# SDRAM.net
KiCad netlist of a schematic drawn in Altium Designer
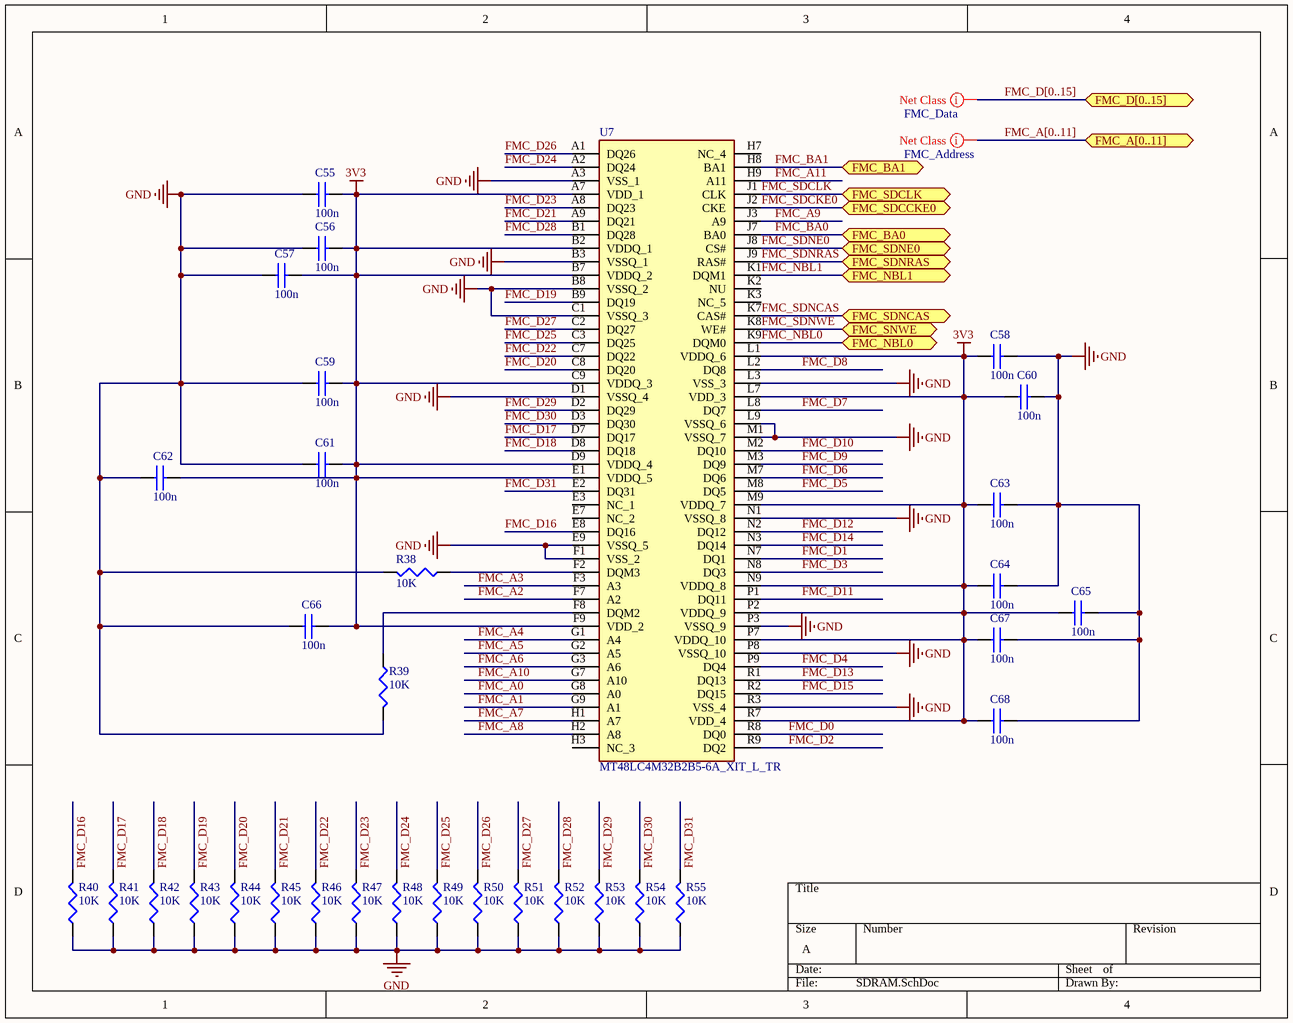
[diagram p0: SDRAM.SchDoc]

(export (version "E")
  (design (tool "Eeschema 10.0.6"))
  (components
    (comp (ref "C55")
      (value "100n")
      (footprint "C0402")
      (description "CAP CER .10UF 50V X5R 10% 0402")
      (fields
        (field (name "MANUFACTURER") "TDK Corporation")
        (field (name "MANUFACTURER PART NUMBER") "C1005X5R1H104K")
      )
      (libsource (lib "iMX6_Rex_Development_Baseboard_V1I1") (part "C1005X5R1H104K"))
    )
    (comp (ref "C56")
      (value "100n")
      (footprint "C0402")
      (description "CAP CER .10UF 50V X5R 10% 0402")
      (fields
        (field (name "MANUFACTURER") "TDK Corporation")
        (field (name "MANUFACTURER PART NUMBER") "C1005X5R1H104K")
      )
      (libsource (lib "iMX6_Rex_Development_Baseboard_V1I1") (part "C1005X5R1H104K"))
    )
    (comp (ref "C57")
      (value "100n")
      (footprint "C0402")
      (description "CAP CER .10UF 50V X5R 10% 0402")
      (fields
        (field (name "MANUFACTURER") "TDK Corporation")
        (field (name "MANUFACTURER PART NUMBER") "C1005X5R1H104K")
      )
      (libsource (lib "iMX6_Rex_Development_Baseboard_V1I1") (part "C1005X5R1H104K"))
    )
    (comp (ref "C58")
      (value "100n")
      (footprint "C0402")
      (description "CAP CER .10UF 50V X5R 10% 0402")
      (fields
        (field (name "MANUFACTURER") "TDK Corporation")
        (field (name "MANUFACTURER PART NUMBER") "C1005X5R1H104K")
      )
      (libsource (lib "iMX6_Rex_Development_Baseboard_V1I1") (part "C1005X5R1H104K"))
    )
    (comp (ref "C59")
      (value "100n")
      (footprint "C0402")
      (description "CAP CER .10UF 50V X5R 10% 0402")
      (fields
        (field (name "MANUFACTURER") "TDK Corporation")
        (field (name "MANUFACTURER PART NUMBER") "C1005X5R1H104K")
      )
      (libsource (lib "iMX6_Rex_Development_Baseboard_V1I1") (part "C1005X5R1H104K"))
    )
    (comp (ref "C60")
      (value "100n")
      (footprint "C0402")
      (description "CAP CER .10UF 50V X5R 10% 0402")
      (fields
        (field (name "MANUFACTURER") "TDK Corporation")
        (field (name "MANUFACTURER PART NUMBER") "C1005X5R1H104K")
      )
      (libsource (lib "iMX6_Rex_Development_Baseboard_V1I1") (part "C1005X5R1H104K"))
    )
    (comp (ref "C61")
      (value "100n")
      (footprint "C0402")
      (description "CAP CER .10UF 50V X5R 10% 0402")
      (fields
        (field (name "MANUFACTURER") "TDK Corporation")
        (field (name "MANUFACTURER PART NUMBER") "C1005X5R1H104K")
      )
      (libsource (lib "iMX6_Rex_Development_Baseboard_V1I1") (part "C1005X5R1H104K"))
    )
    (comp (ref "C62")
      (value "100n")
      (footprint "C0402")
      (description "CAP CER .10UF 50V X5R 10% 0402")
      (fields
        (field (name "MANUFACTURER") "TDK Corporation")
        (field (name "MANUFACTURER PART NUMBER") "C1005X5R1H104K")
      )
      (libsource (lib "iMX6_Rex_Development_Baseboard_V1I1") (part "C1005X5R1H104K"))
    )
    (comp (ref "C63")
      (value "100n")
      (footprint "C0402")
      (description "CAP CER .10UF 50V X5R 10% 0402")
      (fields
        (field (name "MANUFACTURER") "TDK Corporation")
        (field (name "MANUFACTURER PART NUMBER") "C1005X5R1H104K")
      )
      (libsource (lib "iMX6_Rex_Development_Baseboard_V1I1") (part "C1005X5R1H104K"))
    )
    (comp (ref "C64")
      (value "100n")
      (footprint "C0402")
      (description "CAP CER .10UF 50V X5R 10% 0402")
      (fields
        (field (name "MANUFACTURER") "TDK Corporation")
        (field (name "MANUFACTURER PART NUMBER") "C1005X5R1H104K")
      )
      (libsource (lib "iMX6_Rex_Development_Baseboard_V1I1") (part "C1005X5R1H104K"))
    )
    (comp (ref "C65")
      (value "100n")
      (footprint "C0402")
      (description "CAP CER .10UF 50V X5R 10% 0402")
      (fields
        (field (name "MANUFACTURER") "TDK Corporation")
        (field (name "MANUFACTURER PART NUMBER") "C1005X5R1H104K")
      )
      (libsource (lib "iMX6_Rex_Development_Baseboard_V1I1") (part "C1005X5R1H104K"))
    )
    (comp (ref "C66")
      (value "100n")
      (footprint "C0402")
      (description "CAP CER .10UF 50V X5R 10% 0402")
      (fields
        (field (name "MANUFACTURER") "TDK Corporation")
        (field (name "MANUFACTURER PART NUMBER") "C1005X5R1H104K")
      )
      (libsource (lib "iMX6_Rex_Development_Baseboard_V1I1") (part "C1005X5R1H104K"))
    )
    (comp (ref "C67")
      (value "100n")
      (footprint "C0402")
      (description "CAP CER .10UF 50V X5R 10% 0402")
      (fields
        (field (name "MANUFACTURER") "TDK Corporation")
        (field (name "MANUFACTURER PART NUMBER") "C1005X5R1H104K")
      )
      (libsource (lib "iMX6_Rex_Development_Baseboard_V1I1") (part "C1005X5R1H104K"))
    )
    (comp (ref "C68")
      (value "100n")
      (footprint "C0402")
      (description "CAP CER .10UF 50V X5R 10% 0402")
      (fields
        (field (name "MANUFACTURER") "TDK Corporation")
        (field (name "MANUFACTURER PART NUMBER") "C1005X5R1H104K")
      )
      (libsource (lib "iMX6_Rex_Development_Baseboard_V1I1") (part "C1005X5R1H104K"))
    )
    (comp (ref "R38")
      (value "10K")
      (footprint "R0402")
      (description "RES 10.0K OHM 1/16W 1% 0402 SMD")
      (fields
        (field (name "MANUFACTURER") "Yageo")
        (field (name "MANUFACTURER PART NUMBER") "RC0402FR-0710KL")
      )
      (libsource (lib "iMX6_Rex_Development_Baseboard_V1I1") (part "RC0402FR-0710KL"))
    )
    (comp (ref "R39")
      (value "10K")
      (footprint "R0402")
      (description "RES 10.0K OHM 1/16W 1% 0402 SMD")
      (fields
        (field (name "MANUFACTURER") "Yageo")
        (field (name "MANUFACTURER PART NUMBER") "RC0402FR-0710KL")
      )
      (libsource (lib "iMX6_Rex_Development_Baseboard_V1I1") (part "RC0402FR-0710KL"))
    )
    (comp (ref "R40")
      (value "10K")
      (footprint "R0402")
      (description "RES 10.0K OHM 1/16W 1% 0402 SMD")
      (fields
        (field (name "MANUFACTURER") "Yageo")
        (field (name "MANUFACTURER PART NUMBER") "RC0402FR-0710KL")
      )
      (libsource (lib "iMX6_Rex_Development_Baseboard_V1I1") (part "RC0402FR-0710KL"))
    )
    (comp (ref "R41")
      (value "10K")
      (footprint "R0402")
      (description "RES 10.0K OHM 1/16W 1% 0402 SMD")
      (fields
        (field (name "MANUFACTURER") "Yageo")
        (field (name "MANUFACTURER PART NUMBER") "RC0402FR-0710KL")
      )
      (libsource (lib "iMX6_Rex_Development_Baseboard_V1I1") (part "RC0402FR-0710KL"))
    )
    (comp (ref "R42")
      (value "10K")
      (footprint "R0402")
      (description "RES 10.0K OHM 1/16W 1% 0402 SMD")
      (fields
        (field (name "MANUFACTURER") "Yageo")
        (field (name "MANUFACTURER PART NUMBER") "RC0402FR-0710KL")
      )
      (libsource (lib "iMX6_Rex_Development_Baseboard_V1I1") (part "RC0402FR-0710KL"))
    )
    (comp (ref "R43")
      (value "10K")
      (footprint "R0402")
      (description "RES 10.0K OHM 1/16W 1% 0402 SMD")
      (fields
        (field (name "MANUFACTURER") "Yageo")
        (field (name "MANUFACTURER PART NUMBER") "RC0402FR-0710KL")
      )
      (libsource (lib "iMX6_Rex_Development_Baseboard_V1I1") (part "RC0402FR-0710KL"))
    )
    (comp (ref "R44")
      (value "10K")
      (footprint "R0402")
      (description "RES 10.0K OHM 1/16W 1% 0402 SMD")
      (fields
        (field (name "MANUFACTURER") "Yageo")
        (field (name "MANUFACTURER PART NUMBER") "RC0402FR-0710KL")
      )
      (libsource (lib "iMX6_Rex_Development_Baseboard_V1I1") (part "RC0402FR-0710KL"))
    )
    (comp (ref "R45")
      (value "10K")
      (footprint "R0402")
      (description "RES 10.0K OHM 1/16W 1% 0402 SMD")
      (fields
        (field (name "MANUFACTURER") "Yageo")
        (field (name "MANUFACTURER PART NUMBER") "RC0402FR-0710KL")
      )
      (libsource (lib "iMX6_Rex_Development_Baseboard_V1I1") (part "RC0402FR-0710KL"))
    )
    (comp (ref "R46")
      (value "10K")
      (footprint "R0402")
      (description "RES 10.0K OHM 1/16W 1% 0402 SMD")
      (fields
        (field (name "MANUFACTURER") "Yageo")
        (field (name "MANUFACTURER PART NUMBER") "RC0402FR-0710KL")
      )
      (libsource (lib "iMX6_Rex_Development_Baseboard_V1I1") (part "RC0402FR-0710KL"))
    )
    (comp (ref "R47")
      (value "10K")
      (footprint "R0402")
      (description "RES 10.0K OHM 1/16W 1% 0402 SMD")
      (fields
        (field (name "MANUFACTURER") "Yageo")
        (field (name "MANUFACTURER PART NUMBER") "RC0402FR-0710KL")
      )
      (libsource (lib "iMX6_Rex_Development_Baseboard_V1I1") (part "RC0402FR-0710KL"))
    )
    (comp (ref "R48")
      (value "10K")
      (footprint "R0402")
      (description "RES 10.0K OHM 1/16W 1% 0402 SMD")
      (fields
        (field (name "MANUFACTURER") "Yageo")
        (field (name "MANUFACTURER PART NUMBER") "RC0402FR-0710KL")
      )
      (libsource (lib "iMX6_Rex_Development_Baseboard_V1I1") (part "RC0402FR-0710KL"))
    )
    (comp (ref "R49")
      (value "10K")
      (footprint "R0402")
      (description "RES 10.0K OHM 1/16W 1% 0402 SMD")
      (fields
        (field (name "MANUFACTURER") "Yageo")
        (field (name "MANUFACTURER PART NUMBER") "RC0402FR-0710KL")
      )
      (libsource (lib "iMX6_Rex_Development_Baseboard_V1I1") (part "RC0402FR-0710KL"))
    )
    (comp (ref "R50")
      (value "10K")
      (footprint "R0402")
      (description "RES 10.0K OHM 1/16W 1% 0402 SMD")
      (fields
        (field (name "MANUFACTURER") "Yageo")
        (field (name "MANUFACTURER PART NUMBER") "RC0402FR-0710KL")
      )
      (libsource (lib "iMX6_Rex_Development_Baseboard_V1I1") (part "RC0402FR-0710KL"))
    )
    (comp (ref "R51")
      (value "10K")
      (footprint "R0402")
      (description "RES 10.0K OHM 1/16W 1% 0402 SMD")
      (fields
        (field (name "MANUFACTURER") "Yageo")
        (field (name "MANUFACTURER PART NUMBER") "RC0402FR-0710KL")
      )
      (libsource (lib "iMX6_Rex_Development_Baseboard_V1I1") (part "RC0402FR-0710KL"))
    )
    (comp (ref "R52")
      (value "10K")
      (footprint "R0402")
      (description "RES 10.0K OHM 1/16W 1% 0402 SMD")
      (fields
        (field (name "MANUFACTURER") "Yageo")
        (field (name "MANUFACTURER PART NUMBER") "RC0402FR-0710KL")
      )
      (libsource (lib "iMX6_Rex_Development_Baseboard_V1I1") (part "RC0402FR-0710KL"))
    )
    (comp (ref "R53")
      (value "10K")
      (footprint "R0402")
      (description "RES 10.0K OHM 1/16W 1% 0402 SMD")
      (fields
        (field (name "MANUFACTURER") "Yageo")
        (field (name "MANUFACTURER PART NUMBER") "RC0402FR-0710KL")
      )
      (libsource (lib "iMX6_Rex_Development_Baseboard_V1I1") (part "RC0402FR-0710KL"))
    )
    (comp (ref "R54")
      (value "10K")
      (footprint "R0402")
      (description "RES 10.0K OHM 1/16W 1% 0402 SMD")
      (fields
        (field (name "MANUFACTURER") "Yageo")
        (field (name "MANUFACTURER PART NUMBER") "RC0402FR-0710KL")
      )
      (libsource (lib "iMX6_Rex_Development_Baseboard_V1I1") (part "RC0402FR-0710KL"))
    )
    (comp (ref "R55")
      (value "10K")
      (footprint "R0402")
      (description "RES 10.0K OHM 1/16W 1% 0402 SMD")
      (fields
        (field (name "MANUFACTURER") "Yageo")
        (field (name "MANUFACTURER PART NUMBER") "RC0402FR-0710KL")
      )
      (libsource (lib "iMX6_Rex_Development_Baseboard_V1I1") (part "RC0402FR-0710KL"))
    )
    (comp (ref "U7")
      (value "MT48LC4M32B2B5-6A_XIT_L_TR")
      (footprint "SamacSys:BGA90C80P9X15_800X1300X70")
      (description "Integrated Circuit")
      (fields
        (field (name "MANUFACTURER_PART_NUMBER") "MT48LC4M32B2B5-6A XIT:L TR")
        (field (name "MOUSER PART NUMBER") "340-140098-REEL")
      )
      (libsource (lib "*") (part "MT48LC4M32B2B5-6A_XIT_L_TR"))
    )
  )
  (nets
    (net (code "1") (name "/FMC_A0") (class "Default")
      (node (ref "U7") (pin "G8") (pinfunction "A0_G8") (pintype "passive"))
    )
    (net (code "2") (name "/FMC_A1") (class "Default")
      (node (ref "U7") (pin "G9") (pinfunction "A1_G9") (pintype "passive"))
    )
    (net (code "3") (name "/FMC_A2") (class "Default")
      (node (ref "U7") (pin "F7") (pinfunction "A2_F7") (pintype "passive"))
    )
    (net (code "4") (name "/FMC_A3") (class "Default")
      (node (ref "U7") (pin "F3") (pinfunction "A3_F3") (pintype "passive"))
    )
    (net (code "5") (name "/FMC_A4") (class "Default")
      (node (ref "U7") (pin "G1") (pinfunction "A4_G1") (pintype "passive"))
    )
    (net (code "6") (name "/FMC_A5") (class "Default")
      (node (ref "U7") (pin "G2") (pinfunction "A5_G2") (pintype "passive"))
    )
    (net (code "7") (name "/FMC_A6") (class "Default")
      (node (ref "U7") (pin "G3") (pinfunction "A6_G3") (pintype "passive"))
    )
    (net (code "8") (name "/FMC_A7") (class "Default")
      (node (ref "U7") (pin "H1") (pinfunction "A7_H1") (pintype "passive"))
    )
    (net (code "9") (name "/FMC_A8") (class "Default")
      (node (ref "U7") (pin "H2") (pinfunction "A8_H2") (pintype "passive"))
    )
    (net (code "10") (name "/FMC_A9") (class "Default")
      (node (ref "U7") (pin "J3") (pinfunction "A9_J3") (pintype "passive"))
    )
    (net (code "11") (name "/FMC_A10") (class "Default")
      (node (ref "U7") (pin "G7") (pinfunction "A10_G7") (pintype "passive"))
    )
    (net (code "12") (name "/FMC_A11") (class "Default")
      (node (ref "U7") (pin "H9") (pinfunction "A11_H9") (pintype "passive"))
    )
    (net (code "14") (name "/FMC_BA0") (class "Default")
      (node (ref "U7") (pin "J7") (pinfunction "BA0_J7") (pintype "passive"))
    )
    (net (code "15") (name "/FMC_BA1") (class "Default")
      (node (ref "U7") (pin "H8") (pinfunction "BA1_H8") (pintype "passive"))
    )
    (net (code "16") (name "/FMC_D0") (class "Default")
      (node (ref "U7") (pin "R8") (pinfunction "DQ0_R8") (pintype "passive"))
    )
    (net (code "17") (name "/FMC_D1") (class "Default")
      (node (ref "U7") (pin "N7") (pinfunction "DQ1_N7") (pintype "passive"))
    )
    (net (code "18") (name "/FMC_D2") (class "Default")
      (node (ref "U7") (pin "R9") (pinfunction "DQ2_R9") (pintype "passive"))
    )
    (net (code "19") (name "/FMC_D3") (class "Default")
      (node (ref "U7") (pin "N8") (pinfunction "DQ3_N8") (pintype "passive"))
    )
    (net (code "20") (name "/FMC_D4") (class "Default")
      (node (ref "U7") (pin "P9") (pinfunction "DQ4_P9") (pintype "passive"))
    )
    (net (code "21") (name "/FMC_D5") (class "Default")
      (node (ref "U7") (pin "M8") (pinfunction "DQ5_M8") (pintype "passive"))
    )
    (net (code "22") (name "/FMC_D6") (class "Default")
      (node (ref "U7") (pin "M7") (pinfunction "DQ6_M7") (pintype "passive"))
    )
    (net (code "23") (name "/FMC_D7") (class "Default")
      (node (ref "U7") (pin "L8") (pinfunction "DQ7_L8") (pintype "passive"))
    )
    (net (code "24") (name "/FMC_D8") (class "Default")
      (node (ref "U7") (pin "L2") (pinfunction "DQ8_L2") (pintype "passive"))
    )
    (net (code "25") (name "/FMC_D9") (class "Default")
      (node (ref "U7") (pin "M3") (pinfunction "DQ9_M3") (pintype "passive"))
    )
    (net (code "26") (name "/FMC_D10") (class "Default")
      (node (ref "U7") (pin "M2") (pinfunction "DQ10_M2") (pintype "passive"))
    )
    (net (code "27") (name "/FMC_D11") (class "Default")
      (node (ref "U7") (pin "P1") (pinfunction "DQ11_P1") (pintype "passive"))
    )
    (net (code "28") (name "/FMC_D12") (class "Default")
      (node (ref "U7") (pin "N2") (pinfunction "DQ12_N2") (pintype "passive"))
    )
    (net (code "29") (name "/FMC_D13") (class "Default")
      (node (ref "U7") (pin "R1") (pinfunction "DQ13_R1") (pintype "passive"))
    )
    (net (code "30") (name "/FMC_D14") (class "Default")
      (node (ref "U7") (pin "N3") (pinfunction "DQ14_N3") (pintype "passive"))
    )
    (net (code "31") (name "/FMC_D15") (class "Default")
      (node (ref "U7") (pin "R2") (pinfunction "DQ15_R2") (pintype "passive"))
    )
    (net (code "32") (name "/FMC_D16") (class "Default")
      (node (ref "R40") (pin "2") (pinfunction "2_2") (pintype "passive"))
      (node (ref "U7") (pin "E8") (pinfunction "DQ16_E8") (pintype "passive"))
    )
    (net (code "33") (name "/FMC_D17") (class "Default")
      (node (ref "R41") (pin "2") (pinfunction "2_2") (pintype "passive"))
      (node (ref "U7") (pin "D7") (pinfunction "DQ17_D7") (pintype "passive"))
    )
    (net (code "34") (name "/FMC_D18") (class "Default")
      (node (ref "R42") (pin "2") (pinfunction "2_2") (pintype "passive"))
      (node (ref "U7") (pin "D8") (pinfunction "DQ18_D8") (pintype "passive"))
    )
    (net (code "35") (name "/FMC_D19") (class "Default")
      (node (ref "R43") (pin "2") (pinfunction "2_2") (pintype "passive"))
      (node (ref "U7") (pin "B9") (pinfunction "DQ19_B9") (pintype "passive"))
    )
    (net (code "36") (name "/FMC_D20") (class "Default")
      (node (ref "R44") (pin "2") (pinfunction "2_2") (pintype "passive"))
      (node (ref "U7") (pin "C8") (pinfunction "DQ20_C8") (pintype "passive"))
    )
    (net (code "37") (name "/FMC_D21") (class "Default")
      (node (ref "R45") (pin "2") (pinfunction "2_2") (pintype "passive"))
      (node (ref "U7") (pin "A9") (pinfunction "DQ21_A9") (pintype "passive"))
    )
    (net (code "38") (name "/FMC_D22") (class "Default")
      (node (ref "R46") (pin "2") (pinfunction "2_2") (pintype "passive"))
      (node (ref "U7") (pin "C7") (pinfunction "DQ22_C7") (pintype "passive"))
    )
    (net (code "39") (name "/FMC_D23") (class "Default")
      (node (ref "R47") (pin "2") (pinfunction "2_2") (pintype "passive"))
      (node (ref "U7") (pin "A8") (pinfunction "DQ23_A8") (pintype "passive"))
    )
    (net (code "40") (name "/FMC_D24") (class "Default")
      (node (ref "R48") (pin "2") (pinfunction "2_2") (pintype "passive"))
      (node (ref "U7") (pin "A2") (pinfunction "DQ24_A2") (pintype "passive"))
    )
    (net (code "41") (name "/FMC_D25") (class "Default")
      (node (ref "R49") (pin "2") (pinfunction "2_2") (pintype "passive"))
      (node (ref "U7") (pin "C3") (pinfunction "DQ25_C3") (pintype "passive"))
    )
    (net (code "42") (name "/FMC_D26") (class "Default")
      (node (ref "R50") (pin "2") (pinfunction "2_2") (pintype "passive"))
      (node (ref "U7") (pin "A1") (pinfunction "DQ26_A1") (pintype "passive"))
    )
    (net (code "43") (name "/FMC_D27") (class "Default")
      (node (ref "R51") (pin "2") (pinfunction "2_2") (pintype "passive"))
      (node (ref "U7") (pin "C2") (pinfunction "DQ27_C2") (pintype "passive"))
    )
    (net (code "44") (name "/FMC_D28") (class "Default")
      (node (ref "R52") (pin "2") (pinfunction "2_2") (pintype "passive"))
      (node (ref "U7") (pin "B1") (pinfunction "DQ28_B1") (pintype "passive"))
    )
    (net (code "45") (name "/FMC_D29") (class "Default")
      (node (ref "R53") (pin "2") (pinfunction "2_2") (pintype "passive"))
      (node (ref "U7") (pin "D2") (pinfunction "DQ29_D2") (pintype "passive"))
    )
    (net (code "46") (name "/FMC_D30") (class "Default")
      (node (ref "R54") (pin "2") (pinfunction "2_2") (pintype "passive"))
      (node (ref "U7") (pin "D3") (pinfunction "DQ30_D3") (pintype "passive"))
    )
    (net (code "47") (name "/FMC_D31") (class "Default")
      (node (ref "R55") (pin "2") (pinfunction "2_2") (pintype "passive"))
      (node (ref "U7") (pin "E2") (pinfunction "DQ31_E2") (pintype "passive"))
    )
    (net (code "49") (name "/FMC_NBL0") (class "Default")
      (node (ref "U7") (pin "K9") (pinfunction "DQM0_K9") (pintype "passive"))
    )
    (net (code "50") (name "/FMC_NBL1") (class "Default")
      (node (ref "U7") (pin "K1") (pinfunction "DQM1_K1") (pintype "passive"))
    )
    (net (code "51") (name "/FMC_SDCKE0") (class "Default")
      (node (ref "U7") (pin "J2") (pinfunction "CKE_J2") (pintype "passive"))
    )
    (net (code "52") (name "/FMC_SDCLK") (class "Default")
      (node (ref "U7") (pin "J1") (pinfunction "CLK_J1") (pintype "passive"))
    )
    (net (code "53") (name "/FMC_SDNCAS") (class "Default")
      (node (ref "U7") (pin "K7") (pinfunction "CAS#_K7") (pintype "passive"))
    )
    (net (code "54") (name "/FMC_SDNE0") (class "Default")
      (node (ref "U7") (pin "J8") (pinfunction "CS#_J8") (pintype "passive"))
    )
    (net (code "55") (name "/FMC_SDNRAS") (class "Default")
      (node (ref "U7") (pin "J9") (pinfunction "RAS#_J9") (pintype "passive"))
    )
    (net (code "56") (name "/FMC_SDNWE") (class "Default")
      (node (ref "U7") (pin "K8") (pinfunction "WE#_K8") (pintype "passive"))
    )
    (net (code "57") (name "3V3") (class "Default")
      (node (ref "C55") (pin "2") (pinfunction "2_2") (pintype "passive"))
      (node (ref "C56") (pin "2") (pinfunction "2_2") (pintype "passive"))
      (node (ref "C57") (pin "2") (pinfunction "2_2") (pintype "passive"))
      (node (ref "C58") (pin "1") (pinfunction "1_1") (pintype "passive"))
      (node (ref "C59") (pin "2") (pinfunction "2_2") (pintype "passive"))
      (node (ref "C60") (pin "1") (pinfunction "1_1") (pintype "passive"))
      (node (ref "C61") (pin "2") (pinfunction "2_2") (pintype "passive"))
      (node (ref "C62") (pin "2") (pinfunction "2_2") (pintype "passive"))
      (node (ref "C63") (pin "1") (pinfunction "1_1") (pintype "passive"))
      (node (ref "C64") (pin "1") (pinfunction "1_1") (pintype "passive"))
      (node (ref "C65") (pin "1") (pinfunction "1_1") (pintype "passive"))
      (node (ref "C66") (pin "2") (pinfunction "2_2") (pintype "passive"))
      (node (ref "C67") (pin "1") (pinfunction "1_1") (pintype "passive"))
      (node (ref "C68") (pin "1") (pinfunction "1_1") (pintype "passive"))
      (node (ref "U7") (pin "A7") (pinfunction "VDD_1_A7") (pintype "passive"))
      (node (ref "U7") (pin "B2") (pinfunction "VDDQ_1_B2") (pintype "passive"))
      (node (ref "U7") (pin "B7") (pinfunction "VDDQ_2_B7") (pintype "passive"))
      (node (ref "U7") (pin "C9") (pinfunction "VDDQ_3_C9") (pintype "passive"))
      (node (ref "U7") (pin "D9") (pinfunction "VDDQ_4_D9") (pintype "passive"))
      (node (ref "U7") (pin "E1") (pinfunction "VDDQ_5_E1") (pintype "passive"))
      (node (ref "U7") (pin "F9") (pinfunction "VDD_2_F9") (pintype "passive"))
      (node (ref "U7") (pin "L1") (pinfunction "VDDQ_6_L1") (pintype "passive"))
      (node (ref "U7") (pin "L7") (pinfunction "VDD_3_L7") (pintype "passive"))
      (node (ref "U7") (pin "M9") (pinfunction "VDDQ_7_M9") (pintype "passive"))
      (node (ref "U7") (pin "N9") (pinfunction "VDDQ_8_N9") (pintype "passive"))
      (node (ref "U7") (pin "P2") (pinfunction "VDDQ_9_P2") (pintype "passive"))
      (node (ref "U7") (pin "P7") (pinfunction "VDDQ_10_P7") (pintype "passive"))
      (node (ref "U7") (pin "R7") (pinfunction "VDD_4_R7") (pintype "passive"))
    )
    (net (code "58") (name "GND") (class "Default")
      (node (ref "C55") (pin "1") (pinfunction "1_1") (pintype "passive"))
      (node (ref "C56") (pin "1") (pinfunction "1_1") (pintype "passive"))
      (node (ref "C57") (pin "1") (pinfunction "1_1") (pintype "passive"))
      (node (ref "C58") (pin "2") (pinfunction "2_2") (pintype "passive"))
      (node (ref "C59") (pin "1") (pinfunction "1_1") (pintype "passive"))
      (node (ref "C60") (pin "2") (pinfunction "2_2") (pintype "passive"))
      (node (ref "C61") (pin "1") (pinfunction "1_1") (pintype "passive"))
      (node (ref "C62") (pin "1") (pinfunction "1_1") (pintype "passive"))
      (node (ref "C63") (pin "2") (pinfunction "2_2") (pintype "passive"))
      (node (ref "C64") (pin "2") (pinfunction "2_2") (pintype "passive"))
      (node (ref "C65") (pin "2") (pinfunction "2_2") (pintype "passive"))
      (node (ref "C66") (pin "1") (pinfunction "1_1") (pintype "passive"))
      (node (ref "C67") (pin "2") (pinfunction "2_2") (pintype "passive"))
      (node (ref "C68") (pin "2") (pinfunction "2_2") (pintype "passive"))
      (node (ref "R38") (pin "2") (pinfunction "2_2") (pintype "passive"))
      (node (ref "R39") (pin "2") (pinfunction "2_2") (pintype "passive"))
      (node (ref "R40") (pin "1") (pinfunction "1_1") (pintype "passive"))
      (node (ref "R41") (pin "1") (pinfunction "1_1") (pintype "passive"))
      (node (ref "R42") (pin "1") (pinfunction "1_1") (pintype "passive"))
      (node (ref "R43") (pin "1") (pinfunction "1_1") (pintype "passive"))
      (node (ref "R44") (pin "1") (pinfunction "1_1") (pintype "passive"))
      (node (ref "R45") (pin "1") (pinfunction "1_1") (pintype "passive"))
      (node (ref "R46") (pin "1") (pinfunction "1_1") (pintype "passive"))
      (node (ref "R47") (pin "1") (pinfunction "1_1") (pintype "passive"))
      (node (ref "R48") (pin "1") (pinfunction "1_1") (pintype "passive"))
      (node (ref "R49") (pin "1") (pinfunction "1_1") (pintype "passive"))
      (node (ref "R50") (pin "1") (pinfunction "1_1") (pintype "passive"))
      (node (ref "R51") (pin "1") (pinfunction "1_1") (pintype "passive"))
      (node (ref "R52") (pin "1") (pinfunction "1_1") (pintype "passive"))
      (node (ref "R53") (pin "1") (pinfunction "1_1") (pintype "passive"))
      (node (ref "R54") (pin "1") (pinfunction "1_1") (pintype "passive"))
      (node (ref "R55") (pin "1") (pinfunction "1_1") (pintype "passive"))
      (node (ref "U7") (pin "A3") (pinfunction "VSS_1_A3") (pintype "passive"))
      (node (ref "U7") (pin "B3") (pinfunction "VSSQ_1_B3") (pintype "passive"))
      (node (ref "U7") (pin "B8") (pinfunction "VSSQ_2_B8") (pintype "passive"))
      (node (ref "U7") (pin "C1") (pinfunction "VSSQ_3_C1") (pintype "passive"))
      (node (ref "U7") (pin "D1") (pinfunction "VSSQ_4_D1") (pintype "passive"))
      (node (ref "U7") (pin "E9") (pinfunction "VSSQ_5_E9") (pintype "passive"))
      (node (ref "U7") (pin "F1") (pinfunction "VSS_2_F1") (pintype "passive"))
      (node (ref "U7") (pin "L3") (pinfunction "VSS_3_L3") (pintype "passive"))
      (node (ref "U7") (pin "L9") (pinfunction "VSSQ_6_L9") (pintype "passive"))
      (node (ref "U7") (pin "M1") (pinfunction "VSSQ_7_M1") (pintype "passive"))
      (node (ref "U7") (pin "N1") (pinfunction "VSSQ_8_N1") (pintype "passive"))
      (node (ref "U7") (pin "P3") (pinfunction "VSSQ_9_P3") (pintype "passive"))
      (node (ref "U7") (pin "P8") (pinfunction "VSSQ_10_P8") (pintype "passive"))
      (node (ref "U7") (pin "R3") (pinfunction "VSS_4_R3") (pintype "passive"))
    )
    (net (code "59") (name "Net-(U7-DQM2)") (class "Default")
      (node (ref "R39") (pin "1") (pinfunction "1_1") (pintype "passive"))
      (node (ref "U7") (pin "F8") (pinfunction "DQM2_F8") (pintype "passive"))
    )
    (net (code "60") (name "Net-(U7-DQM3)") (class "Default")
      (node (ref "R38") (pin "1") (pinfunction "1_1") (pintype "passive"))
      (node (ref "U7") (pin "F2") (pinfunction "DQM3_F2") (pintype "passive"))
    )
    (net (code "61") (name "unconnected-(U7-NC_1-PadE3)") (class "Default")
      (node (ref "U7") (pin "E3") (pinfunction "NC_1_E3") (pintype "passive"))
    )
    (net (code "62") (name "unconnected-(U7-NC_2-PadE7)") (class "Default")
      (node (ref "U7") (pin "E7") (pinfunction "NC_2_E7") (pintype "passive"))
    )
    (net (code "63") (name "unconnected-(U7-NC_3-PadH3)") (class "Default")
      (node (ref "U7") (pin "H3") (pinfunction "NC_3_H3") (pintype "passive"))
    )
    (net (code "64") (name "unconnected-(U7-NC_4-PadH7)") (class "Default")
      (node (ref "U7") (pin "H7") (pinfunction "NC_4_H7") (pintype "passive"))
    )
    (net (code "65") (name "unconnected-(U7-NC_5-PadK3)") (class "Default")
      (node (ref "U7") (pin "K3") (pinfunction "NC_5_K3") (pintype "passive"))
    )
    (net (code "66") (name "unconnected-(U7-NU-PadK2)") (class "Default")
      (node (ref "U7") (pin "K2") (pinfunction "NU_K2") (pintype "passive"))
    )
  )
)
